# design_block.net
KiCad netlist of a schematic drawn in EAGLE
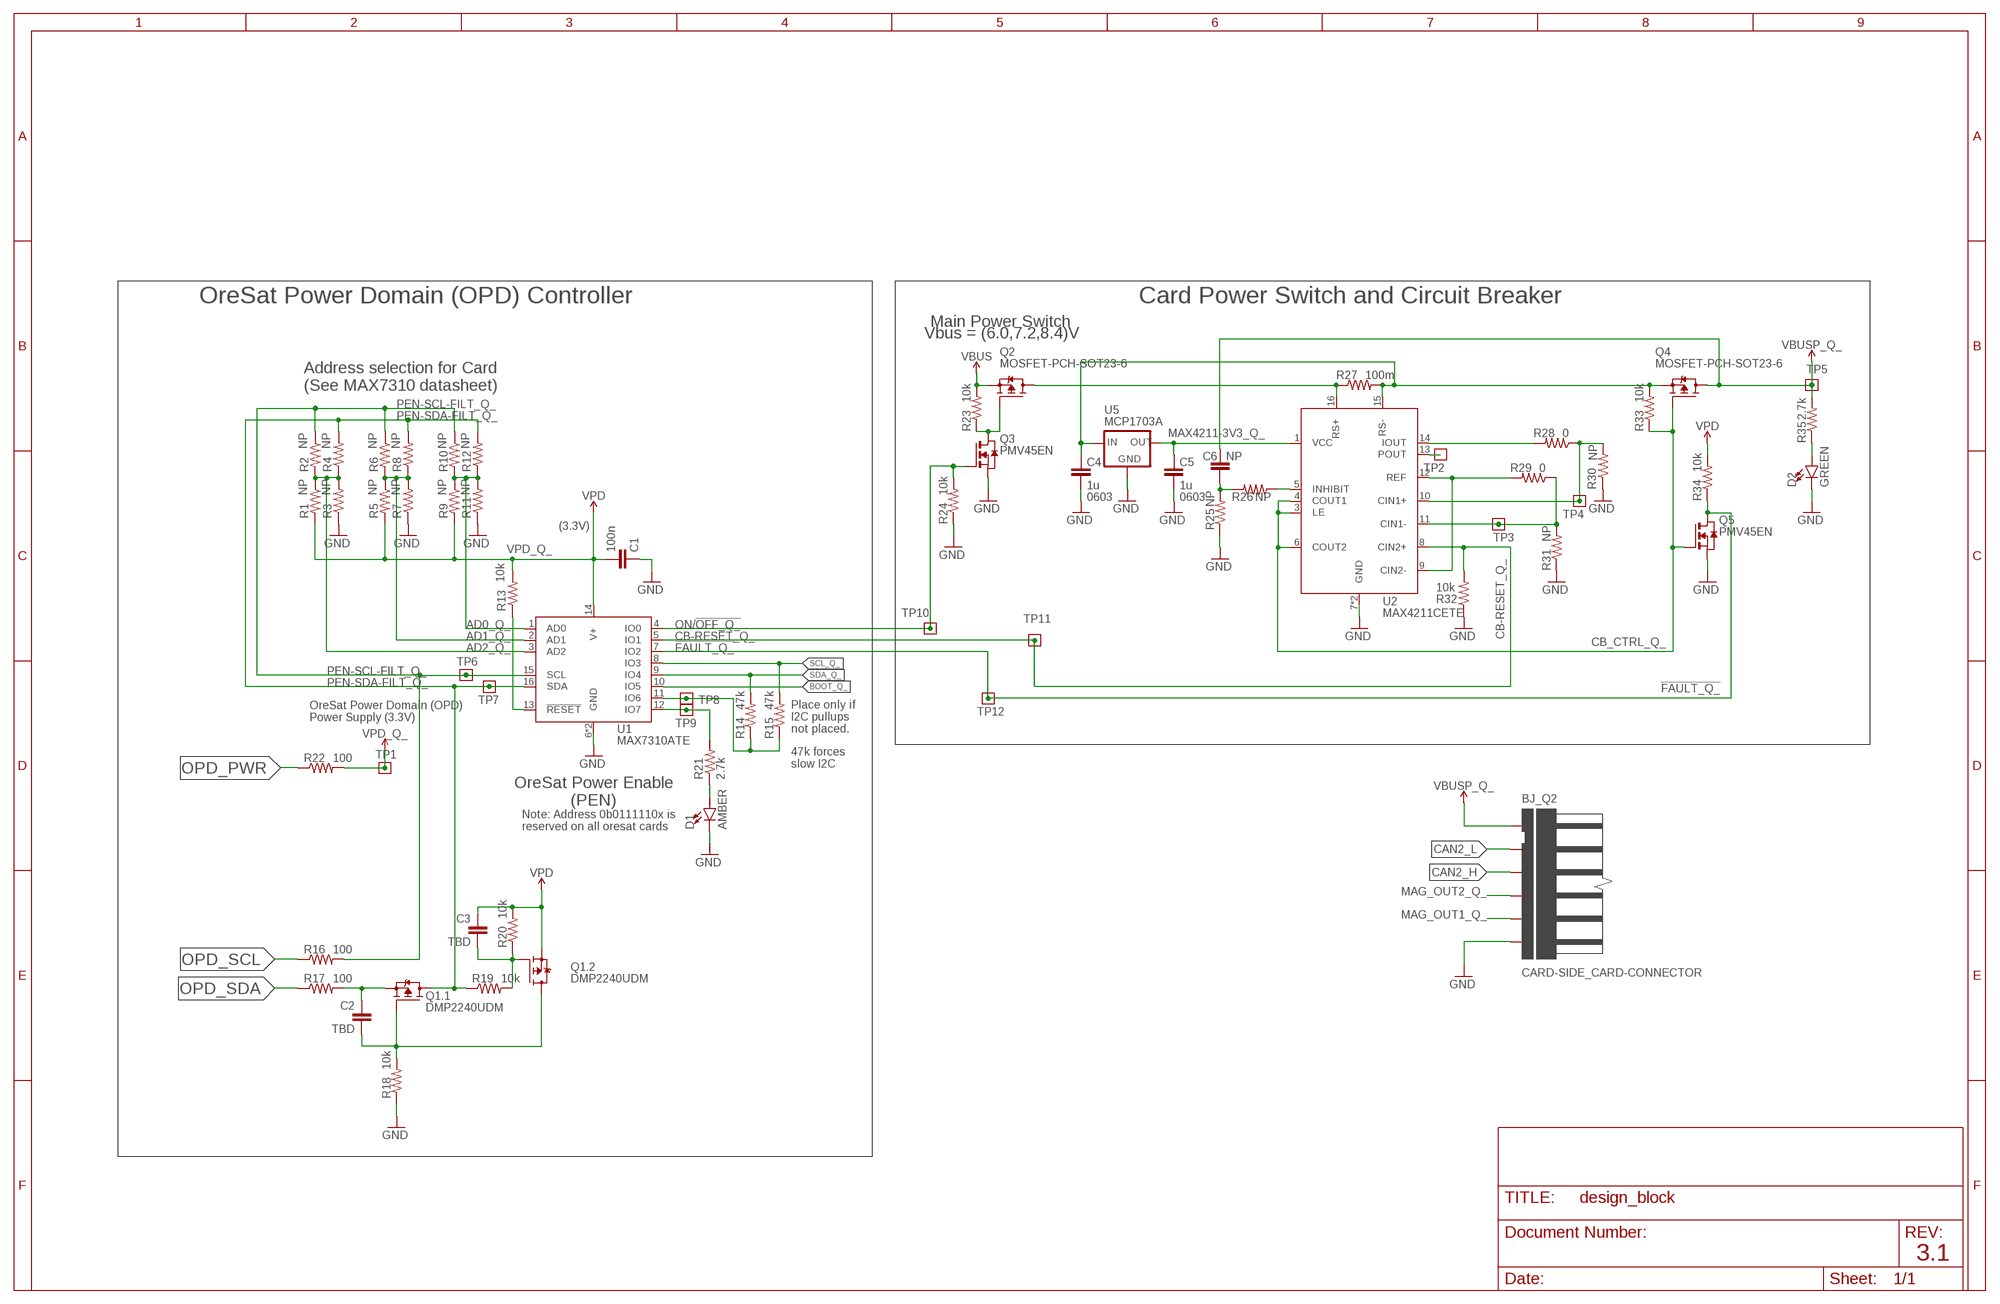
[diagram p0: schematic, sheet 1]

(export (version "E")
  (design (tool "Eeschema 10.0.6"))
  (components
    (comp (ref "BJ_Q2")
      (value "CARD-SIDE_CARD-CONNECTOR")
      (footprint "eagle-import:14-PIN_FFC-PORT")
      (libsource (lib "eagle-import") (part "CARD-SIDE_CARD-CONNECTOR"))
    )
    (comp (ref "C1")
      (value "100n")
      (footprint "eagle-import:.0402-B-NOSILK")
      (fields (field (name "MFR") "Samsung") (field (name "MPN") "CL05B104KO5NNNC"))
      (libsource (lib "eagle-import") (part "rcl_custom_C-EU0402-B-NOSILK"))
    )
    (comp (ref "C2")
      (value "TBD")
      (footprint "eagle-import:.0402-B-NOSILK")
      (fields (field (name "MFR") "Samsung") (field (name "MPN") "CL05B104KO5NNNC"))
      (libsource (lib "eagle-import") (part "rcl_custom_C-EU0402-B-NOSILK"))
    )
    (comp (ref "C3")
      (value "TBD")
      (footprint "eagle-import:.0402-B-NOSILK")
      (fields (field (name "MFR") "Samsung") (field (name "MPN") "CL05B104KO5NNNC"))
      (libsource (lib "eagle-import") (part "rcl_custom_C-EU0402-B-NOSILK"))
    )
    (comp (ref "C4")
      (value "1u")
      (footprint "eagle-import:.0603-B-NOSILK")
      (fields (field (name "MFR") "Samsung") (field (name "MPN") "CL05B104KO5NNNC"))
      (libsource (lib "eagle-import") (part "C-EU0603-B-NOSILK"))
    )
    (comp (ref "C5")
      (value "1u")
      (footprint "eagle-import:.0603-B-NOSILK")
      (fields (field (name "MFR") "Samsung") (field (name "MPN") "CL05B104KO5NNNC"))
      (libsource (lib "eagle-import") (part "C-EU0603-B-NOSILK"))
    )
    (comp (ref "C6")
      (value "NP")
      (footprint "eagle-import:.0402-B-NOSILK")
      (fields (field (name "MFR") "Samsung") (field (name "MPN") "CL05B104KO5NNNC"))
      (libsource (lib "eagle-import") (part "rcl_custom_C-EU0402-B-NOSILK"))
    )
    (comp (ref "D1")
      (value "AMBER")
      (footprint "eagle-import:LED-0603")
      (libsource (lib "eagle-import") (part "LED-GREEN0603"))
    )
    (comp (ref "D2")
      (value "GREEN")
      (footprint "eagle-import:LED-0603")
      (libsource (lib "eagle-import") (part "LED-GREEN0603"))
    )
    (comp (ref "Q1")
      (value "DMP2240UDM")
      (footprint "eagle-import:SOT23-6")
      (fields (field (name "MFR") "Diodes Inc") (field (name "MPN") "DMP2240UDM"))
      (libsource (lib "eagle-import") (part "Q-MOSFET-PCH-dual-SOT23-6_MOSFET-PCH-SOT23-6"))
    )
    (comp (ref "Q2")
      (value "MOSFET-PCH-SOT23-6")
      (footprint "eagle-import:SOT23-6")
      (fields (field (name "MFR") "Diodes Inc") (field (name "MPN") "DMP3050LVT-7"))
      (libsource (lib "eagle-import") (part "MOSFET-PCH-SOT23-6"))
    )
    (comp (ref "Q3")
      (value "PMV45EN")
      (footprint "eagle-import:SOT23")
      (libsource (lib "eagle-import") (part "PMV45EN"))
    )
    (comp (ref "Q4")
      (value "MOSFET-PCH-SOT23-6")
      (footprint "eagle-import:SOT23-6")
      (fields (field (name "MFR") "Diodes Inc") (field (name "MPN") "DMP3050LVT-7"))
      (libsource (lib "eagle-import") (part "MOSFET-PCH-SOT23-6"))
    )
    (comp (ref "Q5")
      (value "PMV45EN")
      (footprint "eagle-import:SOT23")
      (libsource (lib "eagle-import") (part "PMV45EN"))
    )
    (comp (ref "R1")
      (value "NP")
      (footprint "eagle-import:.0402-B-NOSILK")
      (fields (field (name "MFR") "Samsung") (field (name "MPN") "RC1005F6653CS"))
      (libsource (lib "eagle-import") (part "R-US_0402-B-NOSILK"))
    )
    (comp (ref "R2")
      (value "NP")
      (footprint "eagle-import:.0402-B-NOSILK")
      (fields (field (name "MFR") "Samsung") (field (name "MPN") "RC1005F6653CS"))
      (libsource (lib "eagle-import") (part "R-US_0402-B-NOSILK"))
    )
    (comp (ref "R3")
      (value "NP")
      (footprint "eagle-import:.0402-B-NOSILK")
      (fields (field (name "MFR") "Samsung") (field (name "MPN") "RC1005F6653CS"))
      (libsource (lib "eagle-import") (part "R-US_0402-B-NOSILK"))
    )
    (comp (ref "R4")
      (value "NP")
      (footprint "eagle-import:.0402-B-NOSILK")
      (fields (field (name "MFR") "Samsung") (field (name "MPN") "RC1005F6653CS"))
      (libsource (lib "eagle-import") (part "R-US_0402-B-NOSILK"))
    )
    (comp (ref "R5")
      (value "NP")
      (footprint "eagle-import:.0402-B-NOSILK")
      (fields (field (name "MFR") "Samsung") (field (name "MPN") "RC1005F6653CS"))
      (libsource (lib "eagle-import") (part "R-US_0402-B-NOSILK"))
    )
    (comp (ref "R6")
      (value "NP")
      (footprint "eagle-import:.0402-B-NOSILK")
      (fields (field (name "MFR") "Samsung") (field (name "MPN") "RC1005F6653CS"))
      (libsource (lib "eagle-import") (part "R-US_0402-B-NOSILK"))
    )
    (comp (ref "R7")
      (value "NP")
      (footprint "eagle-import:.0402-B-NOSILK")
      (fields (field (name "MFR") "Samsung") (field (name "MPN") "RC1005F6653CS"))
      (libsource (lib "eagle-import") (part "R-US_0402-B-NOSILK"))
    )
    (comp (ref "R8")
      (value "NP")
      (footprint "eagle-import:.0402-B-NOSILK")
      (fields (field (name "MFR") "Samsung") (field (name "MPN") "RC1005F6653CS"))
      (libsource (lib "eagle-import") (part "R-US_0402-B-NOSILK"))
    )
    (comp (ref "R9")
      (value "NP")
      (footprint "eagle-import:.0402-B-NOSILK")
      (fields (field (name "MFR") "Samsung") (field (name "MPN") "RC1005F6653CS"))
      (libsource (lib "eagle-import") (part "R-US_0402-B-NOSILK"))
    )
    (comp (ref "R10")
      (value "NP")
      (footprint "eagle-import:.0402-B-NOSILK")
      (fields (field (name "MFR") "Samsung") (field (name "MPN") "RC1005F6653CS"))
      (libsource (lib "eagle-import") (part "R-US_0402-B-NOSILK"))
    )
    (comp (ref "R11")
      (value "NP")
      (footprint "eagle-import:.0402-B-NOSILK")
      (fields (field (name "MFR") "Samsung") (field (name "MPN") "RC1005F6653CS"))
      (libsource (lib "eagle-import") (part "R-US_0402-B-NOSILK"))
    )
    (comp (ref "R12")
      (value "NP")
      (footprint "eagle-import:.0402-B-NOSILK")
      (fields (field (name "MFR") "Samsung") (field (name "MPN") "RC1005F6653CS"))
      (libsource (lib "eagle-import") (part "R-US_0402-B-NOSILK"))
    )
    (comp (ref "R13")
      (value "10k")
      (footprint "eagle-import:.0402-B-NOSILK")
      (fields (field (name "MFR") "Samsung") (field (name "MPN") "RC1005F6653CS"))
      (libsource (lib "eagle-import") (part "R-US_0402-B-NOSILK"))
    )
    (comp (ref "R14")
      (value "47k")
      (footprint "eagle-import:.0402-B-NOSILK")
      (fields (field (name "MFR") "Samsung") (field (name "MPN") "RC1005F6653CS"))
      (libsource (lib "eagle-import") (part "R-US_0402-B-NOSILK"))
    )
    (comp (ref "R15")
      (value "47k")
      (footprint "eagle-import:.0402-B-NOSILK")
      (fields (field (name "MFR") "Samsung") (field (name "MPN") "RC1005F6653CS"))
      (libsource (lib "eagle-import") (part "R-US_0402-B-NOSILK"))
    )
    (comp (ref "R16")
      (value "100")
      (footprint "eagle-import:.0402-B-NOSILK")
      (fields (field (name "MFR") "Samsung") (field (name "MPN") "RC1005F6653CS"))
      (libsource (lib "eagle-import") (part "R-US_0402-B-NOSILK"))
    )
    (comp (ref "R17")
      (value "100")
      (footprint "eagle-import:.0402-B-NOSILK")
      (fields (field (name "MFR") "Samsung") (field (name "MPN") "RC1005F6653CS"))
      (libsource (lib "eagle-import") (part "R-US_0402-B-NOSILK"))
    )
    (comp (ref "R18")
      (value "10k")
      (footprint "eagle-import:.0402-B-NOSILK")
      (fields (field (name "MFR") "Samsung") (field (name "MPN") "RC1005F6653CS"))
      (libsource (lib "eagle-import") (part "R-US_0402-B-NOSILK"))
    )
    (comp (ref "R19")
      (value "10k")
      (footprint "eagle-import:.0402-B-NOSILK")
      (fields (field (name "MFR") "Samsung") (field (name "MPN") "RC1005F6653CS"))
      (libsource (lib "eagle-import") (part "R-US_0402-B-NOSILK"))
    )
    (comp (ref "R20")
      (value "10k")
      (footprint "eagle-import:.0402-B-NOSILK")
      (fields (field (name "MFR") "Samsung") (field (name "MPN") "RC1005F6653CS"))
      (libsource (lib "eagle-import") (part "R-US_0402-B-NOSILK"))
    )
    (comp (ref "R21")
      (value "2.7k")
      (footprint "eagle-import:.0402-B-NOSILK")
      (fields (field (name "MFR") "Samsung") (field (name "MPN") "RC1005F6653CS"))
      (libsource (lib "eagle-import") (part "R-US_0402-B-NOSILK"))
    )
    (comp (ref "R22")
      (value "100")
      (footprint "eagle-import:.0402-B-NOSILK")
      (fields (field (name "MFR") "Samsung") (field (name "MPN") "RC1005F6653CS"))
      (libsource (lib "eagle-import") (part "R-US_0402-B-NOSILK"))
    )
    (comp (ref "R23")
      (value "10k")
      (footprint "eagle-import:.0402-B-NOSILK")
      (fields (field (name "MFR") "Samsung") (field (name "MPN") "RC1005F6653CS"))
      (libsource (lib "eagle-import") (part "R-US_0402-B-NOSILK"))
    )
    (comp (ref "R24")
      (value "10k")
      (footprint "eagle-import:.0402-B-NOSILK")
      (fields (field (name "MFR") "Samsung") (field (name "MPN") "RC1005F6653CS"))
      (libsource (lib "eagle-import") (part "R-US_0402-B-NOSILK"))
    )
    (comp (ref "R25")
      (value "NP")
      (footprint "eagle-import:.0402-B-NOSILK")
      (fields (field (name "MFR") "Samsung") (field (name "MPN") "RC1005F6653CS"))
      (libsource (lib "eagle-import") (part "R-US_0402-B-NOSILK"))
    )
    (comp (ref "R26")
      (value "NP")
      (footprint "eagle-import:.0402-B-NOSILK")
      (fields (field (name "MFR") "Samsung") (field (name "MPN") "RC1005F6653CS"))
      (libsource (lib "eagle-import") (part "R-US_0402-B-NOSILK"))
    )
    (comp (ref "R27")
      (value "100m")
      (footprint "eagle-import:R1206")
      (libsource (lib "eagle-import") (part "R-US_R1206"))
    )
    (comp (ref "R28")
      (value "0")
      (footprint "eagle-import:.0402-B-NOSILK")
      (fields (field (name "MFR") "Samsung") (field (name "MPN") "RC1005F6653CS"))
      (libsource (lib "eagle-import") (part "R-US_0402-B-NOSILK"))
    )
    (comp (ref "R29")
      (value "0")
      (footprint "eagle-import:.0402-B-NOSILK")
      (fields (field (name "MFR") "Samsung") (field (name "MPN") "RC1005F6653CS"))
      (libsource (lib "eagle-import") (part "R-US_0402-B-NOSILK"))
    )
    (comp (ref "R30")
      (value "NP")
      (footprint "eagle-import:.0402-B-NOSILK")
      (fields (field (name "MFR") "Samsung") (field (name "MPN") "RC1005F6653CS"))
      (libsource (lib "eagle-import") (part "R-US_0402-B-NOSILK"))
    )
    (comp (ref "R31")
      (value "NP")
      (footprint "eagle-import:.0402-B-NOSILK")
      (fields (field (name "MFR") "Samsung") (field (name "MPN") "RC1005F6653CS"))
      (libsource (lib "eagle-import") (part "R-US_0402-B-NOSILK"))
    )
    (comp (ref "R32")
      (value "10k")
      (footprint "eagle-import:.0402-B-NOSILK")
      (fields (field (name "MFR") "Samsung") (field (name "MPN") "RC1005F6653CS"))
      (libsource (lib "eagle-import") (part "R-US_0402-B-NOSILK"))
    )
    (comp (ref "R33")
      (value "10k")
      (footprint "eagle-import:.0402-B-NOSILK")
      (fields (field (name "MFR") "Samsung") (field (name "MPN") "RC1005F6653CS"))
      (libsource (lib "eagle-import") (part "R-US_0402-B-NOSILK"))
    )
    (comp (ref "R34")
      (value "10k")
      (footprint "eagle-import:.0402-B-NOSILK")
      (fields (field (name "MFR") "Samsung") (field (name "MPN") "RC1005F6653CS"))
      (libsource (lib "eagle-import") (part "R-US_0402-B-NOSILK"))
    )
    (comp (ref "R35")
      (value "2.7k")
      (footprint "eagle-import:.0402-B-NOSILK")
      (fields (field (name "MFR") "Samsung") (field (name "MPN") "RC1005F6653CS"))
      (libsource (lib "eagle-import") (part "R-US_0402-B-NOSILK"))
    )
    (comp (ref "TP1")
      (value "TEST-POINT")
      (footprint "eagle-import:2MM-TEST-POINT")
      (libsource (lib "eagle-import") (part "TEST-POINT"))
    )
    (comp (ref "TP2")
      (value "TEST-POINT")
      (footprint "eagle-import:2MM-TEST-POINT")
      (libsource (lib "eagle-import") (part "TEST-POINT"))
    )
    (comp (ref "TP3")
      (value "TEST-POINT")
      (footprint "eagle-import:2MM-TEST-POINT")
      (libsource (lib "eagle-import") (part "TEST-POINT"))
    )
    (comp (ref "TP4")
      (value "TEST-POINT")
      (footprint "eagle-import:2MM-TEST-POINT")
      (libsource (lib "eagle-import") (part "TEST-POINT"))
    )
    (comp (ref "TP5")
      (value "TEST-POINT")
      (footprint "eagle-import:2MM-TEST-POINT")
      (libsource (lib "eagle-import") (part "TEST-POINT"))
    )
    (comp (ref "TP6")
      (value "TEST-POINT")
      (footprint "eagle-import:2MM-TEST-POINT")
      (libsource (lib "eagle-import") (part "TEST-POINT"))
    )
    (comp (ref "TP7")
      (value "TEST-POINT")
      (footprint "eagle-import:2MM-TEST-POINT")
      (libsource (lib "eagle-import") (part "TEST-POINT"))
    )
    (comp (ref "TP8")
      (value "TEST-POINT")
      (footprint "eagle-import:2MM-TEST-POINT")
      (libsource (lib "eagle-import") (part "TEST-POINT"))
    )
    (comp (ref "TP9")
      (value "TEST-POINT")
      (footprint "eagle-import:2MM-TEST-POINT")
      (libsource (lib "eagle-import") (part "TEST-POINT"))
    )
    (comp (ref "TP10")
      (value "TEST-POINT")
      (footprint "eagle-import:2MM-TEST-POINT")
      (libsource (lib "eagle-import") (part "TEST-POINT"))
    )
    (comp (ref "TP11")
      (value "TEST-POINT")
      (footprint "eagle-import:2MM-TEST-POINT")
      (libsource (lib "eagle-import") (part "TEST-POINT"))
    )
    (comp (ref "TP12")
      (value "TEST-POINT")
      (footprint "eagle-import:2MM-TEST-POINT")
      (libsource (lib "eagle-import") (part "TEST-POINT"))
    )
    (comp (ref "U1")
      (value "MAX7310ATE")
      (footprint "eagle-import:QFN65P400X400X80-17T210")
      (fields (field (name "MFR") "Maxim"))
      (libsource (lib "eagle-import") (part "MAX7310"))
    )
    (comp (ref "U2")
      (value "MAX4211CETE")
      (footprint "eagle-import:QFN65P400X400X80-17T210")
      (fields (field (name "MFR") "Maxim"))
      (libsource (lib "eagle-import") (part "MAX4211"))
    )
    (comp (ref "U5")
      (value "MCP1703A")
      (footprint "eagle-import:SOT23")
      (fields (field (name "MFR") "Microchip") (field (name "MPN") "MCP1703AT-3302E/CB"))
      (libsource (lib "eagle-import") (part "XC63FPM"))
    )
  )
  (nets
    (net (code "1") (name "/AD0_Q_") (class "Default")
      (node (ref "R10") (pin "2") (pinfunction "2_2") (pintype "passive"))
      (node (ref "R11") (pin "2") (pinfunction "2_2") (pintype "passive"))
      (node (ref "R12") (pin "1") (pinfunction "1_1") (pintype "passive"))
      (node (ref "R9") (pin "1") (pinfunction "1_1") (pintype "passive"))
      (node (ref "U1") (pin "1") (pinfunction "AD0_1") (pintype "input"))
    )
    (net (code "2") (name "/AD1_Q_") (class "Default")
      (node (ref "R5") (pin "1") (pinfunction "1_1") (pintype "passive"))
      (node (ref "R6") (pin "2") (pinfunction "2_2") (pintype "passive"))
      (node (ref "R7") (pin "2") (pinfunction "2_2") (pintype "passive"))
      (node (ref "R8") (pin "1") (pinfunction "1_1") (pintype "passive"))
      (node (ref "U1") (pin "2") (pinfunction "AD1_2") (pintype "input"))
    )
    (net (code "3") (name "/AD2_Q_") (class "Default")
      (node (ref "R1") (pin "1") (pinfunction "1_1") (pintype "passive"))
      (node (ref "R2") (pin "2") (pinfunction "2_2") (pintype "passive"))
      (node (ref "R3") (pin "2") (pinfunction "2_2") (pintype "passive"))
      (node (ref "R4") (pin "1") (pinfunction "1_1") (pintype "passive"))
      (node (ref "U1") (pin "3") (pinfunction "AD2_3") (pintype "input"))
    )
    (net (code "4") (name "/CB-RESET_Q_") (class "Default")
      (node (ref "R32") (pin "2") (pinfunction "2_2") (pintype "passive"))
      (node (ref "TP11") (pin "1") (pinfunction "1_1") (pintype "passive"))
      (node (ref "U1") (pin "5") (pinfunction "IO1_5") (pintype "bidirectional"))
      (node (ref "U2") (pin "8") (pinfunction "CIN2+_8") (pintype "input"))
    )
    (net (code "5") (name "/CB_CTRL_Q_") (class "Default")
      (node (ref "Q4") (pin "3") (pinfunction "G_3") (pintype "passive"))
      (node (ref "Q5") (pin "1") (pinfunction "G_1") (pintype "passive"))
      (node (ref "R33") (pin "1") (pinfunction "1_1") (pintype "passive"))
      (node (ref "U2") (pin "3") (pinfunction "LE_3") (pintype "input"))
      (node (ref "U2") (pin "4") (pinfunction "COUT1_4") (pintype "open_collector"))
      (node (ref "U2") (pin "6") (pinfunction "COUT2_6") (pintype "open_collector"))
    )
    (net (code "6") (name "/MAG_OUT1_Q_") (class "Default")
      (node (ref "BJ_Q2") (pin "P$10") (pinfunction "P$5_P$10") (pintype "bidirectional"))
      (node (ref "BJ_Q2") (pin "P$11") (pinfunction "P$5_P$11") (pintype "bidirectional"))
    )
    (net (code "7") (name "/MAG_OUT2_Q_") (class "Default")
      (node (ref "BJ_Q2") (pin "P$8") (pinfunction "P$4_P$8") (pintype "bidirectional"))
      (node (ref "BJ_Q2") (pin "P$9") (pinfunction "P$4_P$9") (pintype "bidirectional"))
    )
    (net (code "8") (name "/MAX4211-3V3_Q_") (class "Default")
      (node (ref "C5") (pin "1") (pinfunction "1_1") (pintype "passive"))
      (node (ref "U2") (pin "1") (pinfunction "VCC_1") (pintype "power_in"))
      (node (ref "U5") (pin "2") (pinfunction "OUT_2") (pintype "passive"))
    )
    (net (code "9") (name "/ON{slash}~{OFF_Q_}") (class "Default")
      (node (ref "Q3") (pin "1") (pinfunction "G_1") (pintype "passive"))
      (node (ref "R24") (pin "2") (pinfunction "2_2") (pintype "passive"))
      (node (ref "TP10") (pin "1") (pinfunction "1_1") (pintype "passive"))
      (node (ref "U1") (pin "4") (pinfunction "IO0_4") (pintype "bidirectional"))
    )
    (net (code "10") (name "/PEN-SCL-FILT_Q_") (class "Default")
      (node (ref "R10") (pin "1") (pinfunction "1_1") (pintype "passive"))
      (node (ref "R16") (pin "2") (pinfunction "2_2") (pintype "passive"))
      (node (ref "R2") (pin "1") (pinfunction "1_1") (pintype "passive"))
      (node (ref "R6") (pin "1") (pinfunction "1_1") (pintype "passive"))
      (node (ref "TP6") (pin "1") (pinfunction "1_1") (pintype "passive"))
      (node (ref "U1") (pin "15") (pinfunction "SCL_15") (pintype "input"))
    )
    (net (code "11") (name "/PEN-SDA-FILT_Q_") (class "Default")
      (node (ref "Q1") (pin "6") (pinfunction "D_6") (pintype "passive"))
      (node (ref "R12") (pin "2") (pinfunction "2_2") (pintype "passive"))
      (node (ref "R19") (pin "1") (pinfunction "1_1") (pintype "passive"))
      (node (ref "R4") (pin "2") (pinfunction "2_2") (pintype "passive"))
      (node (ref "R8") (pin "2") (pinfunction "2_2") (pintype "passive"))
      (node (ref "TP7") (pin "1") (pinfunction "1_1") (pintype "passive"))
      (node (ref "U1") (pin "16") (pinfunction "SDA_16") (pintype "bidirectional"))
    )
    (net (code "12") (name "/~{FAULT_Q_}") (class "Default")
      (node (ref "Q5") (pin "3") (pinfunction "D_3") (pintype "passive"))
      (node (ref "R34") (pin "1") (pinfunction "1_1") (pintype "passive"))
      (node (ref "TP12") (pin "1") (pinfunction "1_1") (pintype "passive"))
      (node (ref "U1") (pin "7") (pinfunction "IO2_7") (pintype "bidirectional"))
    )
    (net (code "13") (name "BOOT_Q_") (class "Default")
      (node (ref "U1") (pin "10") (pinfunction "IO5_10") (pintype "bidirectional"))
    )
    (net (code "14") (name "CAN2_H") (class "Default")
      (node (ref "BJ_Q2") (pin "P$6") (pinfunction "P$3_P$6") (pintype "bidirectional"))
      (node (ref "BJ_Q2") (pin "P$7") (pinfunction "P$3_P$7") (pintype "bidirectional"))
    )
    (net (code "15") (name "CAN2_L") (class "Default")
      (node (ref "BJ_Q2") (pin "P$4") (pinfunction "P$2_P$4") (pintype "bidirectional"))
      (node (ref "BJ_Q2") (pin "P$5") (pinfunction "P$2_P$5") (pintype "bidirectional"))
    )
    (net (code "16") (name "GND") (class "Default")
      (node (ref "BJ_Q2") (pin "P$12") (pinfunction "P$6_P$12") (pintype "bidirectional"))
      (node (ref "BJ_Q2") (pin "P$13") (pinfunction "P$6_P$13") (pintype "bidirectional"))
      (node (ref "BJ_Q2") (pin "P$14") (pinfunction "P$6_P$14") (pintype "bidirectional"))
      (node (ref "BJ_Q2") (pin "P$15") (pinfunction "P$6_P$15") (pintype "bidirectional"))
      (node (ref "BJ_Q2") (pin "P$16") (pinfunction "P$6_P$16") (pintype "bidirectional"))
      (node (ref "C1") (pin "1") (pinfunction "1_1") (pintype "passive"))
      (node (ref "C4") (pin "2") (pinfunction "2_2") (pintype "passive"))
      (node (ref "C5") (pin "2") (pinfunction "2_2") (pintype "passive"))
      (node (ref "D1") (pin "C") (pinfunction "C_C") (pintype "passive"))
      (node (ref "D2") (pin "C") (pinfunction "C_C") (pintype "passive"))
      (node (ref "Q3") (pin "2") (pinfunction "S_2") (pintype "passive"))
      (node (ref "Q5") (pin "2") (pinfunction "S_2") (pintype "passive"))
      (node (ref "R11") (pin "1") (pinfunction "1_1") (pintype "passive"))
      (node (ref "R18") (pin "1") (pinfunction "1_1") (pintype "passive"))
      (node (ref "R24") (pin "1") (pinfunction "1_1") (pintype "passive"))
      (node (ref "R25") (pin "1") (pinfunction "1_1") (pintype "passive"))
      (node (ref "R3") (pin "1") (pinfunction "1_1") (pintype "passive"))
      (node (ref "R30") (pin "1") (pinfunction "1_1") (pintype "passive"))
      (node (ref "R31") (pin "1") (pinfunction "1_1") (pintype "passive"))
      (node (ref "R32") (pin "1") (pinfunction "1_1") (pintype "passive"))
      (node (ref "R7") (pin "1") (pinfunction "1_1") (pintype "passive"))
      (node (ref "U1") (pin "6") (pinfunction "GND_6") (pintype "power_in"))
      (node (ref "U1") (pin "EPAD") (pinfunction "GND_EPAD") (pintype "power_in"))
      (node (ref "U2") (pin "7") (pinfunction "GND_7") (pintype "power_in"))
      (node (ref "U2") (pin "EPAD") (pinfunction "GND_EPAD") (pintype "power_in"))
      (node (ref "U5") (pin "1") (pinfunction "GND_1") (pintype "input"))
    )
    (net (code "17") (name "Net-(C6-Pad1)") (class "Default")
      (node (ref "C6") (pin "1") (pinfunction "1_1") (pintype "passive"))
      (node (ref "R25") (pin "2") (pinfunction "2_2") (pintype "passive"))
      (node (ref "R26") (pin "2") (pinfunction "2_2") (pintype "passive"))
    )
    (net (code "18") (name "Net-(D1-PadA)") (class "Default")
      (node (ref "D1") (pin "A") (pinfunction "A_A") (pintype "passive"))
      (node (ref "R21") (pin "1") (pinfunction "1_1") (pintype "passive"))
    )
    (net (code "19") (name "Net-(D2-PadA)") (class "Default")
      (node (ref "D2") (pin "A") (pinfunction "A_A") (pintype "passive"))
      (node (ref "R35") (pin "1") (pinfunction "1_1") (pintype "passive"))
    )
    (net (code "20") (name "Net-(Q1A-G)") (class "Default")
      (node (ref "C2") (pin "2") (pinfunction "2_2") (pintype "passive"))
      (node (ref "Q1") (pin "1") (pinfunction "G_1") (pintype "passive"))
      (node (ref "Q1") (pin "4") (pinfunction "D_4") (pintype "passive"))
      (node (ref "R18") (pin "2") (pinfunction "2_2") (pintype "passive"))
    )
    (net (code "21") (name "Net-(Q1A-S)") (class "Default")
      (node (ref "C2") (pin "1") (pinfunction "1_1") (pintype "passive"))
      (node (ref "Q1") (pin "5") (pinfunction "S_5") (pintype "passive"))
      (node (ref "R17") (pin "2") (pinfunction "2_2") (pintype "passive"))
    )
    (net (code "22") (name "Net-(Q1B-G)") (class "Default")
      (node (ref "C3") (pin "2") (pinfunction "2_2") (pintype "passive"))
      (node (ref "Q1") (pin "3") (pinfunction "G_3") (pintype "passive"))
      (node (ref "R19") (pin "2") (pinfunction "2_2") (pintype "passive"))
      (node (ref "R20") (pin "1") (pinfunction "1_1") (pintype "passive"))
    )
    (net (code "23") (name "Net-(Q2-G)") (class "Default")
      (node (ref "Q2") (pin "3") (pinfunction "G_3") (pintype "passive"))
      (node (ref "Q3") (pin "3") (pinfunction "D_3") (pintype "passive"))
      (node (ref "R23") (pin "1") (pinfunction "1_1") (pintype "passive"))
    )
    (net (code "24") (name "Net-(Q4-S)") (class "Default")
      (node (ref "C4") (pin "1") (pinfunction "1_1") (pintype "passive"))
      (node (ref "Q4") (pin "4") (pinfunction "S_4") (pintype "passive"))
      (node (ref "R27") (pin "2") (pinfunction "2_2") (pintype "passive"))
      (node (ref "R33") (pin "2") (pinfunction "2_2") (pintype "passive"))
      (node (ref "U2") (pin "15") (pinfunction "RS-_15") (pintype "passive"))
      (node (ref "U5") (pin "3") (pinfunction "IN_3") (pintype "input"))
    )
    (net (code "25") (name "Net-(U1-IO6)") (class "Default")
      (node (ref "R14") (pin "1") (pinfunction "1_1") (pintype "passive"))
      (node (ref "R15") (pin "1") (pinfunction "1_1") (pintype "passive"))
      (node (ref "TP8") (pin "1") (pinfunction "1_1") (pintype "passive"))
      (node (ref "U1") (pin "11") (pinfunction "IO6_11") (pintype "bidirectional"))
    )
    (net (code "26") (name "Net-(U1-IO7)") (class "Default")
      (node (ref "R21") (pin "2") (pinfunction "2_2") (pintype "passive"))
      (node (ref "TP9") (pin "1") (pinfunction "1_1") (pintype "passive"))
      (node (ref "U1") (pin "12") (pinfunction "IO7_12") (pintype "bidirectional"))
    )
    (net (code "27") (name "Net-(U1-~{RESET})") (class "Default")
      (node (ref "R13") (pin "1") (pinfunction "1_1") (pintype "passive"))
      (node (ref "U1") (pin "13") (pinfunction "~{RESET}_13") (pintype "input"))
    )
    (net (code "28") (name "Net-(U2-CIN1+)") (class "Default")
      (node (ref "R28") (pin "1") (pinfunction "1_1") (pintype "passive"))
      (node (ref "R30") (pin "2") (pinfunction "2_2") (pintype "passive"))
      (node (ref "TP4") (pin "1") (pinfunction "1_1") (pintype "passive"))
      (node (ref "U2") (pin "10") (pinfunction "CIN1+_10") (pintype "input"))
    )
    (net (code "29") (name "Net-(U2-CIN1-)") (class "Default")
      (node (ref "R29") (pin "1") (pinfunction "1_1") (pintype "passive"))
      (node (ref "R31") (pin "2") (pinfunction "2_2") (pintype "passive"))
      (node (ref "TP3") (pin "1") (pinfunction "1_1") (pintype "passive"))
      (node (ref "U2") (pin "11") (pinfunction "CIN1-_11") (pintype "input"))
    )
    (net (code "30") (name "Net-(U2-CIN2-)") (class "Default")
      (node (ref "R29") (pin "2") (pinfunction "2_2") (pintype "passive"))
      (node (ref "U2") (pin "12") (pinfunction "REF_12") (pintype "output"))
      (node (ref "U2") (pin "9") (pinfunction "CIN2-_9") (pintype "input"))
    )
    (net (code "31") (name "Net-(U2-INHIBIT)") (class "Default")
      (node (ref "R26") (pin "1") (pinfunction "1_1") (pintype "passive"))
      (node (ref "U2") (pin "5") (pinfunction "INHIBIT_5") (pintype "input"))
    )
    (net (code "32") (name "Net-(U2-IOUT)") (class "Default")
      (node (ref "R28") (pin "2") (pinfunction "2_2") (pintype "passive"))
      (node (ref "U2") (pin "14") (pinfunction "IOUT_14") (pintype "output"))
    )
    (net (code "33") (name "Net-(U2-POUT)") (class "Default")
      (node (ref "TP2") (pin "1") (pinfunction "1_1") (pintype "passive"))
      (node (ref "U2") (pin "13") (pinfunction "POUT_13") (pintype "output"))
    )
    (net (code "34") (name "Net-(U2-RS+)") (class "Default")
      (node (ref "Q2") (pin "1") (pinfunction "D_1") (pintype "passive"))
      (node (ref "Q2") (pin "2") (pinfunction "D_2") (pintype "passive"))
      (node (ref "Q2") (pin "5") (pinfunction "D_5") (pintype "passive"))
      (node (ref "Q2") (pin "6") (pinfunction "D_6") (pintype "passive"))
      (node (ref "R27") (pin "1") (pinfunction "1_1") (pintype "passive"))
      (node (ref "U2") (pin "16") (pinfunction "RS+_16") (pintype "passive"))
    )
    (net (code "35") (name "OPD_PWR") (class "Default")
      (node (ref "R22") (pin "1") (pinfunction "1_1") (pintype "passive"))
    )
    (net (code "36") (name "OPD_SCL") (class "Default")
      (node (ref "R16") (pin "1") (pinfunction "1_1") (pintype "passive"))
    )
    (net (code "37") (name "OPD_SDA") (class "Default")
      (node (ref "R17") (pin "1") (pinfunction "1_1") (pintype "passive"))
    )
    (net (code "38") (name "SCL_Q_") (class "Default")
      (node (ref "R15") (pin "2") (pinfunction "2_2") (pintype "passive"))
      (node (ref "U1") (pin "8") (pinfunction "IO3_8") (pintype "bidirectional"))
    )
    (net (code "39") (name "SDA_Q_") (class "Default")
      (node (ref "R14") (pin "2") (pinfunction "2_2") (pintype "passive"))
      (node (ref "U1") (pin "9") (pinfunction "IO4_9") (pintype "bidirectional"))
    )
    (net (code "40") (name "VBUS") (class "Default")
      (node (ref "Q2") (pin "4") (pinfunction "S_4") (pintype "passive"))
      (node (ref "R23") (pin "2") (pinfunction "2_2") (pintype "passive"))
    )
    (net (code "41") (name "VBUSP_Q_") (class "Default")
      (node (ref "BJ_Q2") (pin "P$1") (pinfunction "P$1_P$1") (pintype "bidirectional"))
      (node (ref "BJ_Q2") (pin "P$2") (pinfunction "P$1_P$2") (pintype "bidirectional"))
      (node (ref "BJ_Q2") (pin "P$3") (pinfunction "P$1_P$3") (pintype "bidirectional"))
      (node (ref "C6") (pin "2") (pinfunction "2_2") (pintype "passive"))
      (node (ref "Q4") (pin "1") (pinfunction "D_1") (pintype "passive"))
      (node (ref "Q4") (pin "2") (pinfunction "D_2") (pintype "passive"))
      (node (ref "Q4") (pin "5") (pinfunction "D_5") (pintype "passive"))
      (node (ref "Q4") (pin "6") (pinfunction "D_6") (pintype "passive"))
      (node (ref "R35") (pin "2") (pinfunction "2_2") (pintype "passive"))
      (node (ref "TP5") (pin "1") (pinfunction "1_1") (pintype "passive"))
    )
    (net (code "42") (name "VPD") (class "Default")
      (node (ref "C1") (pin "2") (pinfunction "2_2") (pintype "passive"))
      (node (ref "C3") (pin "1") (pinfunction "1_1") (pintype "passive"))
      (node (ref "Q1") (pin "2") (pinfunction "S_2") (pintype "passive"))
      (node (ref "R1") (pin "2") (pinfunction "2_2") (pintype "passive"))
      (node (ref "R13") (pin "2") (pinfunction "2_2") (pintype "passive"))
      (node (ref "R20") (pin "2") (pinfunction "2_2") (pintype "passive"))
      (node (ref "R22") (pin "2") (pinfunction "2_2") (pintype "passive"))
      (node (ref "R34") (pin "2") (pinfunction "2_2") (pintype "passive"))
      (node (ref "R5") (pin "2") (pinfunction "2_2") (pintype "passive"))
      (node (ref "R9") (pin "2") (pinfunction "2_2") (pintype "passive"))
      (node (ref "TP1") (pin "1") (pinfunction "1_1") (pintype "passive"))
      (node (ref "U1") (pin "14") (pinfunction "V+_14") (pintype "power_in"))
    )
  )
)
